# TRNG_ying_0_2.net
KiCad netlist of a schematic drawn in Altium Designer
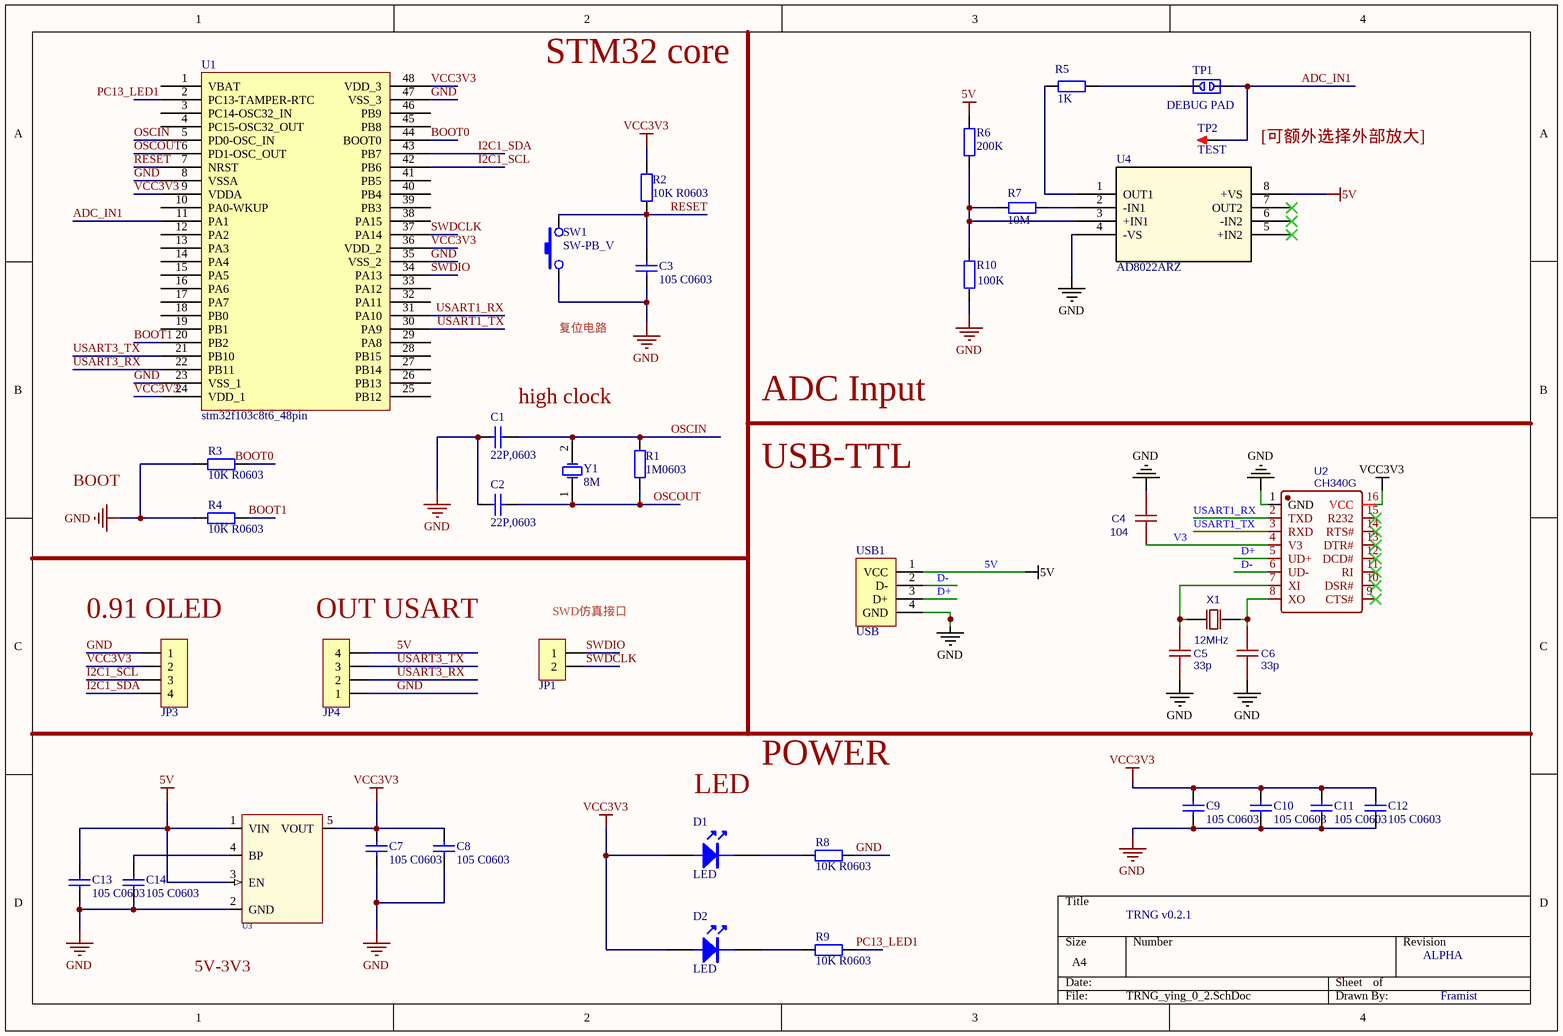
[diagram p0: TRNG_ying_0_2.SchDoc]

(export (version "E")
  (design (tool "Eeschema 10.0.6"))
  (components
    (comp (ref "C1")
      (value "22P,0603")
      (footprint "C 0603")
      (description "Capacitor")
      (fields (field (name "PUBLISHER") "Altium Limited"))
      (libsource (lib "STM32F103C8T6") (part "Cap"))
    )
    (comp (ref "C2")
      (value "22P,0603")
      (footprint "C 0603")
      (description "Capacitor")
      (fields (field (name "PUBLISHER") "Altium Limited"))
      (libsource (lib "STM32F103C8T6") (part "Cap"))
    )
    (comp (ref "C3")
      (value "105 C0603")
      (footprint "C 0603")
      (fields (field (name "PUBLISHER") "Altium Limited"))
      (libsource (lib "stm32原理图库") (part "Cap"))
    )
    (comp (ref "C4")
      (value "104")
      (footprint "C 0603")
      (fields
        (field (name "BOM_SUPPLIER PART") "C472790")
        (field (name "BOM_MANUFACTURER PART") "CL10C330JC81PNC")
        (field (name "CONTRIBUTOR") "LCSC")
      )
      (libsource (lib "altium-import") (part "root_1_104_"))
    )
    (comp (ref "C5")
      (value "33p")
      (footprint "C 0603")
      (fields
        (field (name "BOM_SUPPLIER PART") "C472790")
        (field (name "BOM_MANUFACTURER PART") "CL10C330JC81PNC")
        (field (name "CONTRIBUTOR") "LCSC")
      )
      (libsource (lib "altium-import") (part "root_1_33p_"))
    )
    (comp (ref "C6")
      (value "33p")
      (footprint "C 0603")
      (fields
        (field (name "BOM_SUPPLIER PART") "C472790")
        (field (name "BOM_MANUFACTURER PART") "CL10C330JC81PNC")
        (field (name "CONTRIBUTOR") "LCSC")
      )
      (libsource (lib "altium-import") (part "root_1_33p_"))
    )
    (comp (ref "C7")
      (value "105 C0603")
      (footprint "C 0603")
      (fields (field (name "PUBLISHER") "Altium Limited"))
      (libsource (lib "stm32原理图库") (part "Cap"))
    )
    (comp (ref "C8")
      (value "105 C0603")
      (footprint "C 0603")
      (fields (field (name "PUBLISHER") "Altium Limited"))
      (libsource (lib "stm32原理图库") (part "Cap"))
    )
    (comp (ref "C9")
      (value "105 C0603")
      (footprint "C 0603")
      (fields (field (name "PUBLISHER") "Altium Limited"))
      (libsource (lib "stm32原理图库") (part "Cap"))
    )
    (comp (ref "C10")
      (value "105 C0603")
      (footprint "C 0603")
      (fields (field (name "PUBLISHER") "Altium Limited"))
      (libsource (lib "stm32原理图库") (part "Cap"))
    )
    (comp (ref "C11")
      (value "105 C0603")
      (footprint "C 0603")
      (fields (field (name "PUBLISHER") "Altium Limited"))
      (libsource (lib "stm32原理图库") (part "Cap"))
    )
    (comp (ref "C12")
      (value "105 C0603")
      (footprint "C 0603")
      (fields (field (name "PUBLISHER") "Altium Limited"))
      (libsource (lib "stm32原理图库") (part "Cap"))
    )
    (comp (ref "C13")
      (value "105 C0603")
      (footprint "C 0603")
      (fields (field (name "PUBLISHER") "Altium Limited"))
      (libsource (lib "stm32原理图库") (part "Cap"))
    )
    (comp (ref "C14")
      (value "105 C0603")
      (footprint "C 0603")
      (fields (field (name "PUBLISHER") "Altium Limited"))
      (libsource (lib "stm32原理图库") (part "Cap"))
    )
    (comp (ref "D1") (value "LED") (footprint "LED 0805G") (libsource (lib "stm32原理图库") (part "LED")))
    (comp (ref "D2") (value "LED") (footprint "LED 0805G") (libsource (lib "stm32原理图库") (part "LED")))
    (comp (ref "JP1")
      (value "HDR-1X2")
      (footprint "HDR2.54 S-W-2P")
      (description "2P接插件")
      (fields (field (name "版权归属") "源创客"))
      (libsource (lib "接插件") (part "Header 2"))
    )
    (comp (ref "JP3")
      (value "HDR-1X4")
      (footprint "HDR-1X4")
      (description "4P接插件")
      (fields (field (name "版权归属") "源创客"))
      (libsource (lib "") (part "Header 4_1"))
    )
    (comp (ref "JP4")
      (value "HDR-1X4")
      (footprint "HDR-1X4")
      (description "4P接插件")
      (fields (field (name "版权归属") "源创客"))
      (libsource (lib "接插件") (part "Header 4"))
    )
    (comp (ref "R1")
      (value "1M0603")
      (footprint "R 0603")
      (description "Resistor")
      (fields (field (name "PUBLISHER") "Altium Limited"))
      (libsource (lib "STM32F103C8T6") (part "Res2"))
    )
    (comp (ref "R2")
      (value "10K R0603")
      (footprint "R 0603")
      (fields (field (name "PUBLISHER") "Altium Limited"))
      (libsource (lib "stm32原理图库") (part "Res2"))
    )
    (comp (ref "R3")
      (value "10K R0603")
      (footprint "R 0603")
      (fields (field (name "PUBLISHER") "Altium Limited"))
      (libsource (lib "") (part "Res2_2"))
    )
    (comp (ref "R4")
      (value "10K R0603")
      (footprint "R 0603")
      (fields (field (name "PUBLISHER") "Altium Limited"))
      (libsource (lib "") (part "Res2_1"))
    )
    (comp (ref "R5")
      (value "1K")
      (footprint "R 0603")
      (description "贴片电阻")
      (fields (field (name "版权归属") "源创客"))
      (libsource (lib "电阻-电容-电感") (part "R"))
    )
    (comp (ref "R6")
      (value "200K")
      (footprint "R 0603")
      (description "贴片电阻")
      (fields (field (name "版权归属") "源创客"))
      (libsource (lib "电阻-电容-电感") (part "R"))
    )
    (comp (ref "R7")
      (value "10M")
      (footprint "R 0603")
      (description "贴片电阻")
      (fields (field (name "版权归属") "源创客"))
      (libsource (lib "电阻-电容-电感") (part "R"))
    )
    (comp (ref "R8")
      (value "10K R0603")
      (footprint "R 0603")
      (fields (field (name "PUBLISHER") "Altium Limited"))
      (libsource (lib "") (part "Res2_1"))
    )
    (comp (ref "R9")
      (value "10K R0603")
      (footprint "R 0603")
      (fields (field (name "PUBLISHER") "Altium Limited"))
      (libsource (lib "") (part "Res2_1"))
    )
    (comp (ref "R10")
      (value "100K")
      (footprint "R 0603")
      (description "贴片电阻")
      (fields (field (name "版权归属") "源创客"))
      (libsource (lib "电阻-电容-电感") (part "R"))
    )
    (comp (ref "SW1")
      (value "SW-PB_V")
      (footprint "TSW SMD-3*6*2.5")
      (libsource (lib "stm32原理图库") (part "SW-PB_V"))
    )
    (comp (ref "TP1")
      (value "DEBUG PAD")
      (footprint "DEBUG PAD2")
      (description "调试断点焊盘")
      (fields (field (name "版权归属") "源创客"))
      (libsource (lib "未分类器件") (part "DEBUG"))
    )
    (comp (ref "TP2")
      (value "TEST")
      (footprint "TEST 1")
      (description "测试点")
      (fields (field (name "版权归属") "源创客"))
      (libsource (lib "未分类器件") (part "TEST"))
    )
    (comp (ref "U1")
      (value "stm32f103c8t6_48pin")
      (footprint "TQFP48 7x7_L")
      (libsource (lib "STM32_Schlib") (part "stm32f103c8t6_48pin"))
    )
    (comp (ref "U2")
      (value "CH340G")
      (footprint "SOP16_M")
      (fields (field (name "BOM_SUPPLIER PART") "C14267"))
      (libsource (lib "altium-import") (part "root_0_CH340G_"))
    )
    (comp (ref "U3")
      (value "RT9193")
      (footprint "SOT23-5L")
      (fields (field (name "ICA_PARTNUM") "$$2191094$$RT9193-15CU5") (field (name "PART NUMBER") "TMP-13"))
      (libsource (lib "stm32原理图库") (part "RT9193X_5P"))
    )
    (comp (ref "U4")
      (value "AD8022ARZ")
      (footprint "R_8_ADI-M")
      (description "AD8022内置两个低噪声、高速、电压反馈型放大器")
      (fields (field (name "COPYRIGHT") "Copyright (C) 2021 Ultra Librarian. All rights reserved."))
      (libsource (lib "AD8022ARZ") (part "AD8022ARZ"))
    )
    (comp (ref "USB1")
      (value "USB")
      (footprint "USB_A/P_A")
      (description "USB-A型公接口")
      (fields (field (name "版权归属") "源创客"))
      (libsource (lib "接口类") (part "USB-A/P"))
    )
    (comp (ref "X1")
      (value "12MHz")
      (footprint "XTAL-3225")
      (fields
        (field (name "BOM_SUPPLIER PART") "C295065")
        (field (name "BOM_MANUFACTURER PART") "XSHEELNANF-12MHZ")
        (field (name "CONTRIBUTOR") "LCSC")
      )
      (libsource (lib "altium-import") (part "root_2_12MHz_"))
    )
    (comp (ref "Y1")
      (value "8M")
      (footprint "XTAL-5032")
      (description "Crystal Oscillator")
      (fields (field (name "PUBLISHER") "Altium Limited"))
      (libsource (lib "STM32F103C8T6") (part "XTAL"))
    )
  )
  (nets
    (net (code "1") (name "/ADC_IN1") (class "Default")
      (node (ref "TP1") (pin "2") (pinfunction "2_2") (pintype "passive"))
      (node (ref "TP2") (pin "1") (pinfunction "1_1") (pintype "passive"))
      (node (ref "U1") (pin "11") (pinfunction "PA1_11") (pintype "passive"))
    )
    (net (code "2") (name "/BOOT0") (class "Default")
      (node (ref "R3") (pin "1") (pinfunction "1_1") (pintype "passive"))
      (node (ref "U1") (pin "44") (pinfunction "BOOT0_44") (pintype "passive"))
    )
    (net (code "3") (name "/BOOT1") (class "Default")
      (node (ref "R4") (pin "2") (pinfunction "2_2") (pintype "passive"))
      (node (ref "U1") (pin "20") (pinfunction "PB2_20") (pintype "passive"))
    )
    (net (code "4") (name "/D+") (class "Default")
      (node (ref "U2") (pin "5") (pinfunction "UD+_5") (pintype "passive"))
      (node (ref "USB1") (pin "3") (pinfunction "D+_3") (pintype "passive"))
    )
    (net (code "5") (name "/D-") (class "Default")
      (node (ref "U2") (pin "6") (pinfunction "UD-_6") (pintype "passive"))
      (node (ref "USB1") (pin "2") (pinfunction "D-_2") (pintype "passive"))
    )
    (net (code "6") (name "/I2C1_SCL") (class "Default")
      (node (ref "JP3") (pin "3") (pinfunction "3_3") (pintype "passive"))
      (node (ref "U1") (pin "42") (pinfunction "PB6_42") (pintype "passive"))
    )
    (net (code "7") (name "/I2C1_SDA") (class "Default")
      (node (ref "JP3") (pin "4") (pinfunction "4_4") (pintype "passive"))
      (node (ref "U1") (pin "43") (pinfunction "PB7_43") (pintype "passive"))
    )
    (net (code "8") (name "/OSCIN") (class "Default")
      (node (ref "C1") (pin "1") (pinfunction "1_1") (pintype "passive"))
      (node (ref "R1") (pin "2") (pinfunction "2_2") (pintype "passive"))
      (node (ref "U1") (pin "5") (pinfunction "PD0-OSC_IN_5") (pintype "passive"))
      (node (ref "Y1") (pin "2") (pinfunction "OSC2_2") (pintype "passive"))
    )
    (net (code "9") (name "/OSCOUT") (class "Default")
      (node (ref "C2") (pin "1") (pinfunction "1_1") (pintype "passive"))
      (node (ref "R1") (pin "1") (pinfunction "1_1") (pintype "passive"))
      (node (ref "U1") (pin "6") (pinfunction "PD1-OSC_OUT_6") (pintype "passive"))
      (node (ref "Y1") (pin "1") (pinfunction "OSC1_1") (pintype "passive"))
    )
    (net (code "10") (name "/PC13_LED1") (class "Default")
      (node (ref "R9") (pin "2") (pinfunction "2_2") (pintype "passive"))
      (node (ref "U1") (pin "2") (pinfunction "PC13-TAMPER-RTC_2") (pintype "passive"))
    )
    (net (code "11") (name "/RESET") (class "Default")
      (node (ref "C3") (pin "2") (pinfunction "2_2") (pintype "passive"))
      (node (ref "R2") (pin "1") (pinfunction "1_1") (pintype "passive"))
      (node (ref "SW1") (pin "2") (pinfunction "2_2") (pintype "passive"))
      (node (ref "U1") (pin "7") (pinfunction "NRST_7") (pintype "passive"))
    )
    (net (code "12") (name "/SWDCLK") (class "Default")
      (node (ref "JP1") (pin "2") (pinfunction "2_2") (pintype "passive"))
      (node (ref "U1") (pin "37") (pinfunction "PA14_37") (pintype "passive"))
    )
    (net (code "13") (name "/SWDIO") (class "Default")
      (node (ref "JP1") (pin "1") (pinfunction "1_1") (pintype "passive"))
      (node (ref "U1") (pin "34") (pinfunction "PA13_34") (pintype "passive"))
    )
    (net (code "14") (name "/USART1_RX") (class "Default")
      (node (ref "U1") (pin "31") (pinfunction "PA10_31") (pintype "passive"))
      (node (ref "U2") (pin "2") (pinfunction "TXD_2") (pintype "passive"))
    )
    (net (code "15") (name "/USART1_TX") (class "Default")
      (node (ref "U1") (pin "30") (pinfunction "PA9_30") (pintype "passive"))
      (node (ref "U2") (pin "3") (pinfunction "RXD_3") (pintype "passive"))
    )
    (net (code "16") (name "/USART3_RX") (class "Default")
      (node (ref "JP4") (pin "2") (pinfunction "2_2") (pintype "passive"))
      (node (ref "U1") (pin "22") (pinfunction "PB11_22") (pintype "passive"))
    )
    (net (code "17") (name "/USART3_TX") (class "Default")
      (node (ref "JP4") (pin "3") (pinfunction "3_3") (pintype "passive"))
      (node (ref "U1") (pin "21") (pinfunction "PB10_21") (pintype "passive"))
    )
    (net (code "18") (name "/V3") (class "Default")
      (node (ref "C4") (pin "1") (pinfunction "1_1") (pintype "passive"))
      (node (ref "U2") (pin "4") (pinfunction "V3_4") (pintype "passive"))
    )
    (net (code "19") (name "5V") (class "Default")
      (node (ref "C13") (pin "2") (pinfunction "2_2") (pintype "passive"))
      (node (ref "JP4") (pin "4") (pinfunction "4_4") (pintype "passive"))
      (node (ref "R6") (pin "1") (pinfunction "1_1") (pintype "passive"))
      (node (ref "U3") (pin "1") (pinfunction "VIN_1") (pintype "power_in"))
      (node (ref "U3") (pin "3") (pinfunction "EN_3") (pintype "input"))
      (node (ref "U4") (pin "8") (pinfunction "+VS_8") (pintype "power_in"))
      (node (ref "USB1") (pin "1") (pinfunction "VCC_1") (pintype "passive"))
    )
    (net (code "20") (name "GND") (class "Default")
      (node (ref "C1") (pin "2") (pinfunction "2_2") (pintype "passive"))
      (node (ref "C10") (pin "1") (pinfunction "1_1") (pintype "passive"))
      (node (ref "C11") (pin "1") (pinfunction "1_1") (pintype "passive"))
      (node (ref "C12") (pin "1") (pinfunction "1_1") (pintype "passive"))
      (node (ref "C13") (pin "1") (pinfunction "1_1") (pintype "passive"))
      (node (ref "C14") (pin "1") (pinfunction "1_1") (pintype "passive"))
      (node (ref "C2") (pin "2") (pinfunction "2_2") (pintype "passive"))
      (node (ref "C3") (pin "1") (pinfunction "1_1") (pintype "passive"))
      (node (ref "C4") (pin "2") (pinfunction "2_2") (pintype "passive"))
      (node (ref "C5") (pin "1") (pinfunction "1_1") (pintype "passive"))
      (node (ref "C6") (pin "1") (pinfunction "1_1") (pintype "passive"))
      (node (ref "C7") (pin "1") (pinfunction "1_1") (pintype "passive"))
      (node (ref "C8") (pin "1") (pinfunction "1_1") (pintype "passive"))
      (node (ref "C9") (pin "1") (pinfunction "1_1") (pintype "passive"))
      (node (ref "JP3") (pin "1") (pinfunction "1_1") (pintype "passive"))
      (node (ref "JP4") (pin "1") (pinfunction "1_1") (pintype "passive"))
      (node (ref "R10") (pin "2") (pinfunction "2_2") (pintype "passive"))
      (node (ref "R3") (pin "2") (pinfunction "2_2") (pintype "passive"))
      (node (ref "R4") (pin "1") (pinfunction "1_1") (pintype "passive"))
      (node (ref "R8") (pin "2") (pinfunction "2_2") (pintype "passive"))
      (node (ref "SW1") (pin "1") (pinfunction "1_1") (pintype "passive"))
      (node (ref "U1") (pin "23") (pinfunction "VSS_1_23") (pintype "passive"))
      (node (ref "U1") (pin "35") (pinfunction "VSS_2_35") (pintype "passive"))
      (node (ref "U1") (pin "47") (pinfunction "VSS_3_47") (pintype "passive"))
      (node (ref "U1") (pin "8") (pinfunction "VSSA_8") (pintype "passive"))
      (node (ref "U2") (pin "1") (pinfunction "GND_1") (pintype "passive"))
      (node (ref "U3") (pin "2") (pinfunction "GND_2") (pintype "power_in"))
      (node (ref "U4") (pin "4") (pinfunction "-VS_4") (pintype "power_in"))
      (node (ref "USB1") (pin "4") (pinfunction "GND_4") (pintype "passive"))
    )
    (net (code "21") (name "Net-(D1-Pad2)") (class "Default")
      (node (ref "D1") (pin "2") (pinfunction "2_2") (pintype "passive"))
      (node (ref "R8") (pin "1") (pinfunction "1_1") (pintype "passive"))
    )
    (net (code "22") (name "Net-(D2-Pad2)") (class "Default")
      (node (ref "D2") (pin "2") (pinfunction "2_2") (pintype "passive"))
      (node (ref "R9") (pin "1") (pinfunction "1_1") (pintype "passive"))
    )
    (net (code "23") (name "Net-(R5-Pad2)") (class "Default")
      (node (ref "R5") (pin "2") (pinfunction "2_2") (pintype "passive"))
      (node (ref "TP1") (pin "1") (pinfunction "1_1") (pintype "passive"))
    )
    (net (code "24") (name "Net-(U2-XI)") (class "Default")
      (node (ref "C5") (pin "2") (pinfunction "2_2") (pintype "passive"))
      (node (ref "U2") (pin "7") (pinfunction "XI_7") (pintype "passive"))
      (node (ref "X1") (pin "2") (pinfunction "OSC2_2") (pintype "passive"))
    )
    (net (code "25") (name "Net-(U2-XO)") (class "Default")
      (node (ref "C6") (pin "2") (pinfunction "2_2") (pintype "passive"))
      (node (ref "U2") (pin "8") (pinfunction "XO_8") (pintype "passive"))
      (node (ref "X1") (pin "1") (pinfunction "OSC1_1") (pintype "passive"))
    )
    (net (code "26") (name "Net-(U3-BP)") (class "Default")
      (node (ref "C14") (pin "2") (pinfunction "2_2") (pintype "passive"))
      (node (ref "U3") (pin "4") (pinfunction "BP_4") (pintype "passive"))
    )
    (net (code "27") (name "Net-(U4-+IN1)") (class "Default")
      (node (ref "R10") (pin "1") (pinfunction "1_1") (pintype "passive"))
      (node (ref "R6") (pin "2") (pinfunction "2_2") (pintype "passive"))
      (node (ref "R7") (pin "1") (pinfunction "1_1") (pintype "passive"))
      (node (ref "U4") (pin "3") (pinfunction "+IN1_3") (pintype "passive"))
    )
    (net (code "28") (name "Net-(U4--IN1)") (class "Default")
      (node (ref "R7") (pin "2") (pinfunction "2_2") (pintype "passive"))
      (node (ref "U4") (pin "2") (pinfunction "-IN1_2") (pintype "passive"))
    )
    (net (code "29") (name "Net-(U4-OUT1)") (class "Default")
      (node (ref "R5") (pin "1") (pinfunction "1_1") (pintype "passive"))
      (node (ref "U4") (pin "1") (pinfunction "OUT1_1") (pintype "passive"))
    )
    (net (code "30") (name "VCC3V3") (class "Default")
      (node (ref "C10") (pin "2") (pinfunction "2_2") (pintype "passive"))
      (node (ref "C11") (pin "2") (pinfunction "2_2") (pintype "passive"))
      (node (ref "C12") (pin "2") (pinfunction "2_2") (pintype "passive"))
      (node (ref "C7") (pin "2") (pinfunction "2_2") (pintype "passive"))
      (node (ref "C8") (pin "2") (pinfunction "2_2") (pintype "passive"))
      (node (ref "C9") (pin "2") (pinfunction "2_2") (pintype "passive"))
      (node (ref "D1") (pin "1") (pinfunction "1_1") (pintype "passive"))
      (node (ref "D2") (pin "1") (pinfunction "1_1") (pintype "passive"))
      (node (ref "JP3") (pin "2") (pinfunction "2_2") (pintype "passive"))
      (node (ref "R2") (pin "2") (pinfunction "2_2") (pintype "passive"))
      (node (ref "U1") (pin "24") (pinfunction "VDD_1_24") (pintype "passive"))
      (node (ref "U1") (pin "36") (pinfunction "VDD_2_36") (pintype "passive"))
      (node (ref "U1") (pin "48") (pinfunction "VDD_3_48") (pintype "passive"))
      (node (ref "U1") (pin "9") (pinfunction "VDDA_9") (pintype "passive"))
      (node (ref "U2") (pin "16") (pinfunction "VCC_16") (pintype "passive"))
      (node (ref "U3") (pin "5") (pinfunction "VOUT_5") (pintype "power_in"))
    )
    (net (code "31") (name "unconnected-(U1-PA0-WKUP-Pad10)") (class "Default")
      (node (ref "U1") (pin "10") (pinfunction "PA0-WKUP_10") (pintype "passive"))
    )
    (net (code "32") (name "unconnected-(U1-PA2-Pad12)") (class "Default")
      (node (ref "U1") (pin "12") (pinfunction "PA2_12") (pintype "passive"))
    )
    (net (code "33") (name "unconnected-(U1-PA3-Pad13)") (class "Default")
      (node (ref "U1") (pin "13") (pinfunction "PA3_13") (pintype "passive"))
    )
    (net (code "34") (name "unconnected-(U1-PA4-Pad14)") (class "Default")
      (node (ref "U1") (pin "14") (pinfunction "PA4_14") (pintype "passive"))
    )
    (net (code "35") (name "unconnected-(U1-PA5-Pad15)") (class "Default")
      (node (ref "U1") (pin "15") (pinfunction "PA5_15") (pintype "passive"))
    )
    (net (code "36") (name "unconnected-(U1-PA6-Pad16)") (class "Default")
      (node (ref "U1") (pin "16") (pinfunction "PA6_16") (pintype "passive"))
    )
    (net (code "37") (name "unconnected-(U1-PA7-Pad17)") (class "Default")
      (node (ref "U1") (pin "17") (pinfunction "PA7_17") (pintype "passive"))
    )
    (net (code "38") (name "unconnected-(U1-PA8-Pad29)") (class "Default")
      (node (ref "U1") (pin "29") (pinfunction "PA8_29") (pintype "passive"))
    )
    (net (code "39") (name "unconnected-(U1-PA11-Pad32)") (class "Default")
      (node (ref "U1") (pin "32") (pinfunction "PA11_32") (pintype "passive"))
    )
    (net (code "40") (name "unconnected-(U1-PA12-Pad33)") (class "Default")
      (node (ref "U1") (pin "33") (pinfunction "PA12_33") (pintype "passive"))
    )
    (net (code "41") (name "unconnected-(U1-PA15-Pad38)") (class "Default")
      (node (ref "U1") (pin "38") (pinfunction "PA15_38") (pintype "passive"))
    )
    (net (code "42") (name "unconnected-(U1-PB0-Pad18)") (class "Default")
      (node (ref "U1") (pin "18") (pinfunction "PB0_18") (pintype "passive"))
    )
    (net (code "43") (name "unconnected-(U1-PB1-Pad19)") (class "Default")
      (node (ref "U1") (pin "19") (pinfunction "PB1_19") (pintype "passive"))
    )
    (net (code "44") (name "unconnected-(U1-PB3-Pad39)") (class "Default")
      (node (ref "U1") (pin "39") (pinfunction "PB3_39") (pintype "passive"))
    )
    (net (code "45") (name "unconnected-(U1-PB4-Pad40)") (class "Default")
      (node (ref "U1") (pin "40") (pinfunction "PB4_40") (pintype "passive"))
    )
    (net (code "46") (name "unconnected-(U1-PB5-Pad41)") (class "Default")
      (node (ref "U1") (pin "41") (pinfunction "PB5_41") (pintype "passive"))
    )
    (net (code "47") (name "unconnected-(U1-PB8-Pad45)") (class "Default")
      (node (ref "U1") (pin "45") (pinfunction "PB8_45") (pintype "passive"))
    )
    (net (code "48") (name "unconnected-(U1-PB9-Pad46)") (class "Default")
      (node (ref "U1") (pin "46") (pinfunction "PB9_46") (pintype "passive"))
    )
    (net (code "49") (name "unconnected-(U1-PB12-Pad25)") (class "Default")
      (node (ref "U1") (pin "25") (pinfunction "PB12_25") (pintype "passive"))
    )
    (net (code "50") (name "unconnected-(U1-PB13-Pad26)") (class "Default")
      (node (ref "U1") (pin "26") (pinfunction "PB13_26") (pintype "passive"))
    )
    (net (code "51") (name "unconnected-(U1-PB14-Pad27)") (class "Default")
      (node (ref "U1") (pin "27") (pinfunction "PB14_27") (pintype "passive"))
    )
    (net (code "52") (name "unconnected-(U1-PB15-Pad28)") (class "Default")
      (node (ref "U1") (pin "28") (pinfunction "PB15_28") (pintype "passive"))
    )
    (net (code "53") (name "unconnected-(U1-PC14-OSC32_IN-Pad3)") (class "Default")
      (node (ref "U1") (pin "3") (pinfunction "PC14-OSC32_IN_3") (pintype "passive"))
    )
    (net (code "54") (name "unconnected-(U1-PC15-OSC32_OUT-Pad4)") (class "Default")
      (node (ref "U1") (pin "4") (pinfunction "PC15-OSC32_OUT_4") (pintype "passive"))
    )
    (net (code "55") (name "unconnected-(U1-VBAT-Pad1)") (class "Default")
      (node (ref "U1") (pin "1") (pinfunction "VBAT_1") (pintype "passive"))
    )
    (net (code "56") (name "unconnected-(U2-CTS#-Pad9)") (class "Default")
      (node (ref "U2") (pin "9") (pinfunction "CTS#_9") (pintype "passive+no_connect"))
    )
    (net (code "57") (name "unconnected-(U2-DCD#-Pad12)") (class "Default")
      (node (ref "U2") (pin "12") (pinfunction "DCD#_12") (pintype "passive+no_connect"))
    )
    (net (code "58") (name "unconnected-(U2-DSR#-Pad10)") (class "Default")
      (node (ref "U2") (pin "10") (pinfunction "DSR#_10") (pintype "passive+no_connect"))
    )
    (net (code "59") (name "unconnected-(U2-DTR#-Pad13)") (class "Default")
      (node (ref "U2") (pin "13") (pinfunction "DTR#_13") (pintype "passive+no_connect"))
    )
    (net (code "60") (name "unconnected-(U2-R232-Pad15)") (class "Default")
      (node (ref "U2") (pin "15") (pinfunction "R232_15") (pintype "passive+no_connect"))
    )
    (net (code "61") (name "unconnected-(U2-RI-Pad11)") (class "Default")
      (node (ref "U2") (pin "11") (pinfunction "RI_11") (pintype "passive+no_connect"))
    )
    (net (code "62") (name "unconnected-(U2-RTS#-Pad14)") (class "Default")
      (node (ref "U2") (pin "14") (pinfunction "RTS#_14") (pintype "passive+no_connect"))
    )
    (net (code "63") (name "unconnected-(U4-+IN2-Pad5)") (class "Default")
      (node (ref "U4") (pin "5") (pinfunction "+IN2_5") (pintype "passive+no_connect"))
    )
    (net (code "64") (name "unconnected-(U4--IN2-Pad6)") (class "Default")
      (node (ref "U4") (pin "6") (pinfunction "-IN2_6") (pintype "passive+no_connect"))
    )
    (net (code "65") (name "unconnected-(U4-OUT2-Pad7)") (class "Default")
      (node (ref "U4") (pin "7") (pinfunction "OUT2_7") (pintype "passive+no_connect"))
    )
  )
)
